# pin_matrix_schematic.net
KiCad netlist of a schematic drawn in EAGLE
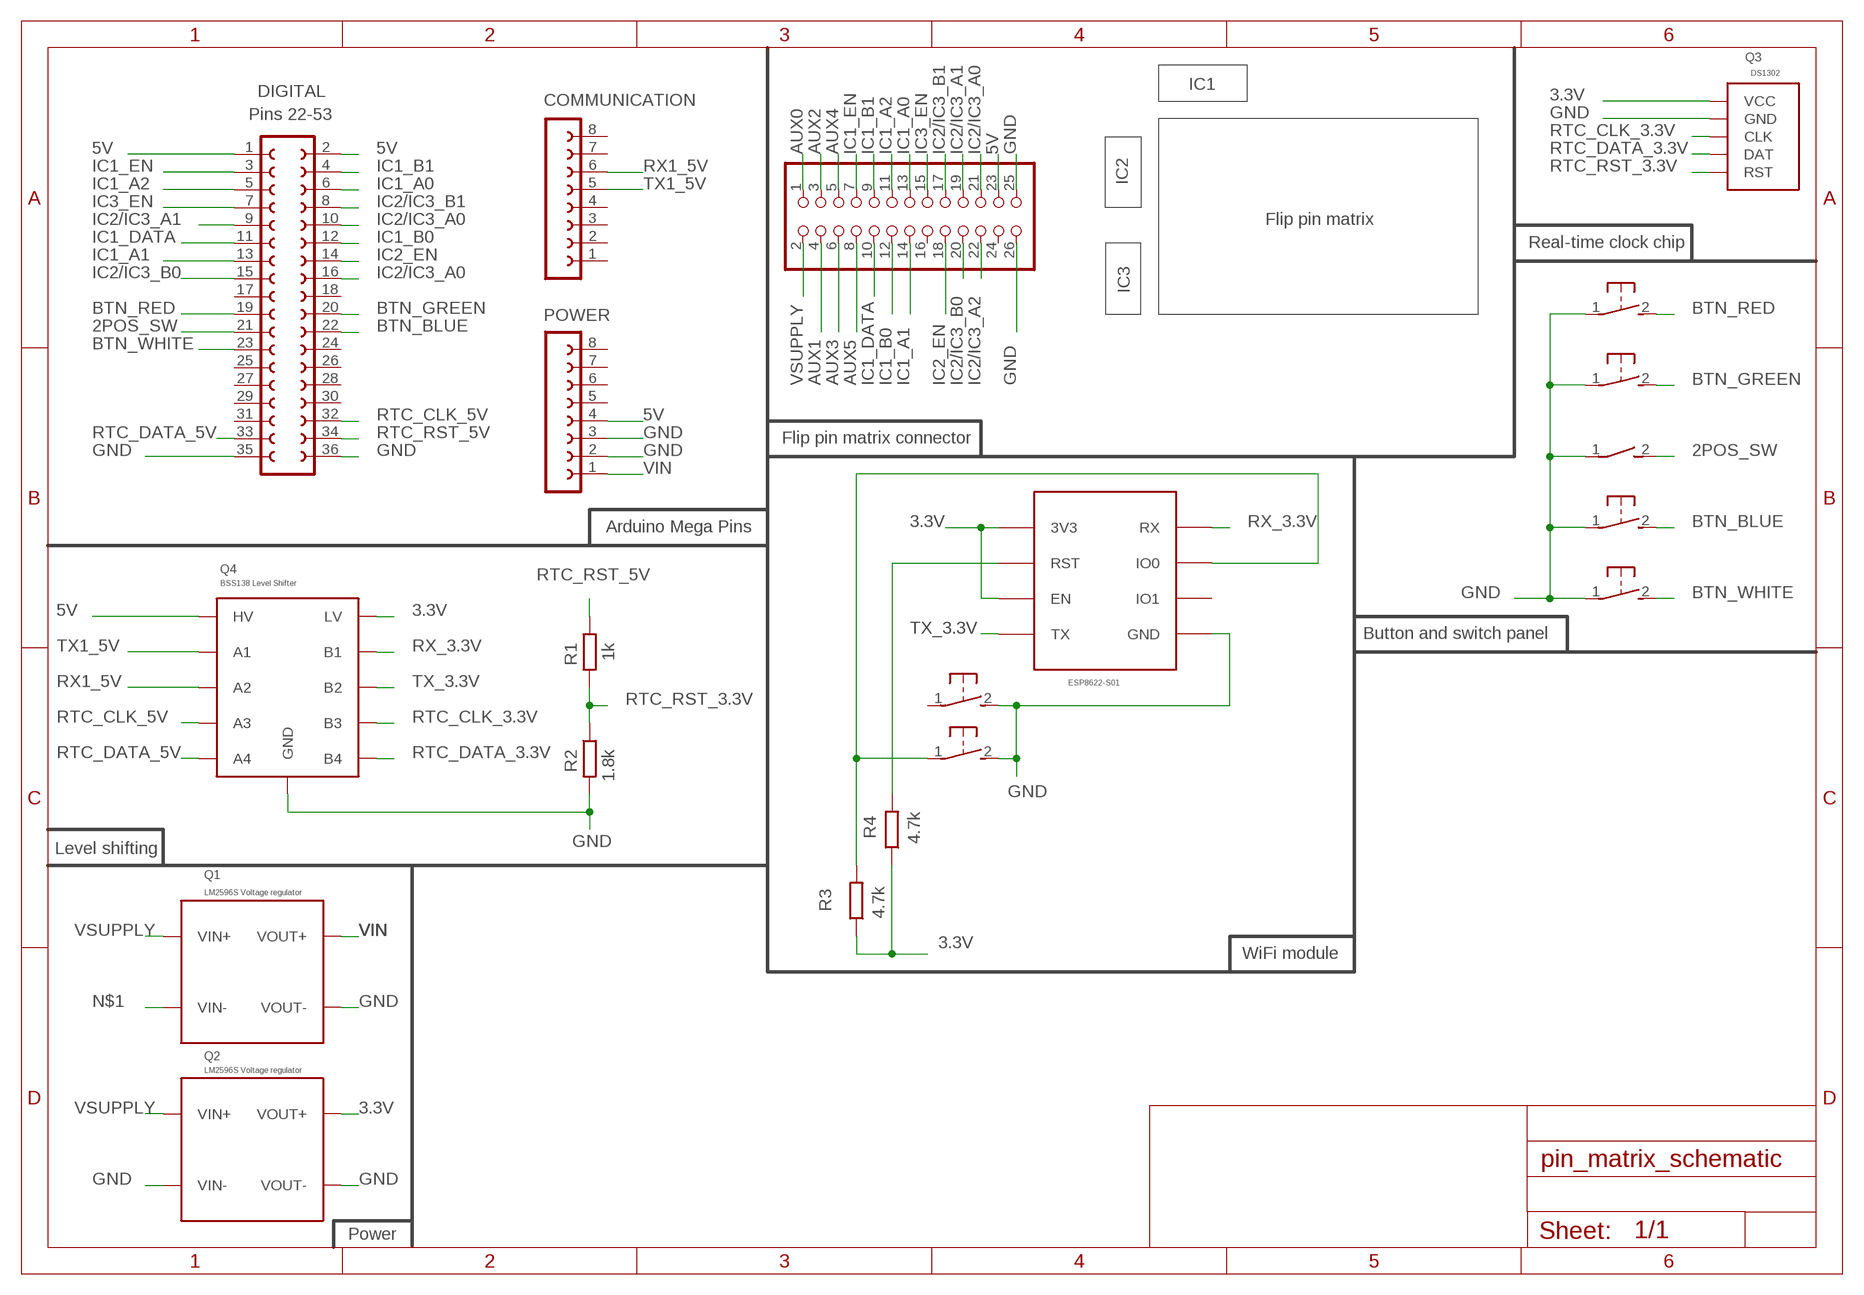
[diagram p0: schematic, sheet 1]

(export (version "E")
  (design (tool "Eeschema 10.0.6"))
  (components
    (comp (ref "COMMUNICATION")
      (value "FE08-1")
      (footprint "eagle-import:FE08")
      (libsource (lib "eagle-import") (part "FE08-1"))
    )
    (comp (ref "DIGITAL")
      (value "Pins 22-53")
      (footprint "eagle-import:FE18-2")
      (libsource (lib "eagle-import") (part "FE18-2"))
    )
    (comp (ref "JP1")
      (value "PINHD-2X13")
      (footprint "eagle-import:2X13")
      (libsource (lib "eagle-import") (part "PINHD-2X13"))
    )
    (comp (ref "POWER")
      (value "FE08-1")
      (footprint "eagle-import:FE08")
      (libsource (lib "eagle-import") (part "FE08-1"))
    )
    (comp (ref "Q1")
      (value "LM2596S-DCDC-BRD")
      (footprint "eagle-import:LM2596S-FOOT")
      (libsource (lib "eagle-import") (part "LM2596S-DCDC-BRD"))
    )
    (comp (ref "Q2")
      (value "LM2596S-DCDC-BRD")
      (footprint "eagle-import:LM2596S-FOOT")
      (libsource (lib "eagle-import") (part "LM2596S-DCDC-BRD"))
    )
    (comp (ref "Q3")
      (value "DS1302-BRD")
      (footprint "eagle-import:DS1302-FOOT")
      (libsource (lib "eagle-import") (part "DS1302-BRD"))
    )
    (comp (ref "Q4")
      (value "BSS138-4CH-LVL-BRD")
      (footprint "eagle-import:BSS138-LVL-FOOT")
      (libsource (lib "eagle-import") (part "BSS138-4CH-LVL-BRD"))
    )
    (comp (ref "Q5")
      (value "ESP1866-01S")
      (footprint "eagle-import:ESP8622-01S-FOOT")
      (libsource (lib "eagle-import") (part "ESP1866-01S"))
    )
    (comp (ref "R1")
      (value "1k")
      (footprint "eagle-import:0204_7")
      (libsource (lib "eagle-import") (part "R-EU_0204/7"))
    )
    (comp (ref "R2")
      (value "1.8k")
      (footprint "eagle-import:0204_7")
      (libsource (lib "eagle-import") (part "R-EU_0204/7"))
    )
    (comp (ref "R3")
      (value "4.7k")
      (footprint "eagle-import:0204_7")
      (libsource (lib "eagle-import") (part "R-EU_0204/7"))
    )
    (comp (ref "R4")
      (value "4.7k")
      (footprint "eagle-import:0204_7")
      (libsource (lib "eagle-import") (part "R-EU_0204/7"))
    )
    (comp (ref "S1")
      (value "DS01E")
      (footprint "eagle-import:DS-01")
      (libsource (lib "eagle-import") (part "DS01E"))
    )
    (comp (ref "S2")
      (value "31-XX")
      (footprint "eagle-import:B3F-31XX")
      (fields (field (name "MPN") "B3F-3100"))
      (libsource (lib "eagle-import") (part "31-XX"))
    )
    (comp (ref "S3")
      (value "31-XX")
      (footprint "eagle-import:B3F-31XX")
      (fields (field (name "MPN") "B3F-3100"))
      (libsource (lib "eagle-import") (part "31-XX"))
    )
    (comp (ref "S4")
      (value "31-XX")
      (footprint "eagle-import:B3F-31XX")
      (fields (field (name "MPN") "B3F-3100"))
      (libsource (lib "eagle-import") (part "31-XX"))
    )
    (comp (ref "S5")
      (value "31-XX")
      (footprint "eagle-import:B3F-31XX")
      (fields (field (name "MPN") "B3F-3100"))
      (libsource (lib "eagle-import") (part "31-XX"))
    )
    (comp (ref "S6")
      (value "31-XX")
      (footprint "eagle-import:B3F-31XX")
      (fields (field (name "MPN") "B3F-3100"))
      (libsource (lib "eagle-import") (part "31-XX"))
    )
    (comp (ref "S7")
      (value "31-XX")
      (footprint "eagle-import:B3F-31XX")
      (fields (field (name "MPN") "B3F-3100"))
      (libsource (lib "eagle-import") (part "31-XX"))
    )
  )
  (nets
    (net (code "1") (name "/2POS_SW") (class "Default")
      (node (ref "DIGITAL") (pin "21") (pinfunction "21_21") (pintype "passive"))
      (node (ref "S1") (pin "2") (pinfunction "2_2") (pintype "passive"))
    )
    (net (code "2") (name "/3.3V") (class "Default")
      (node (ref "Q2") (pin "VOUT+") (pinfunction "VOUT+_VOUT+") (pintype "power_in"))
      (node (ref "Q3") (pin "VCC") (pinfunction "VCC_VCC") (pintype "power_in"))
      (node (ref "Q4") (pin "LV") (pinfunction "LV_LV") (pintype "power_in"))
      (node (ref "Q5") (pin "3V3") (pinfunction "3V3_3V3") (pintype "power_in"))
      (node (ref "Q5") (pin "EN") (pinfunction "EN_EN") (pintype "input"))
      (node (ref "R3") (pin "1") (pinfunction "1_1") (pintype "passive"))
      (node (ref "R4") (pin "1") (pinfunction "1_1") (pintype "passive"))
    )
    (net (code "3") (name "/5V") (class "Default")
      (node (ref "DIGITAL") (pin "1") (pinfunction "1_1") (pintype "passive"))
      (node (ref "DIGITAL") (pin "2") (pinfunction "2_2") (pintype "passive"))
      (node (ref "JP1") (pin "23") (pinfunction "23_23") (pintype "passive"))
      (node (ref "POWER") (pin "4") (pinfunction "4_4") (pintype "passive"))
      (node (ref "Q4") (pin "HV") (pinfunction "HV_HV") (pintype "power_in"))
    )
    (net (code "4") (name "/AUX0") (class "Default")
      (node (ref "JP1") (pin "1") (pinfunction "1_1") (pintype "passive"))
    )
    (net (code "5") (name "/AUX1") (class "Default")
      (node (ref "JP1") (pin "4") (pinfunction "4_4") (pintype "passive"))
    )
    (net (code "6") (name "/AUX2") (class "Default")
      (node (ref "JP1") (pin "3") (pinfunction "3_3") (pintype "passive"))
    )
    (net (code "7") (name "/AUX3") (class "Default")
      (node (ref "JP1") (pin "6") (pinfunction "6_6") (pintype "passive"))
    )
    (net (code "8") (name "/AUX4") (class "Default")
      (node (ref "JP1") (pin "5") (pinfunction "5_5") (pintype "passive"))
    )
    (net (code "9") (name "/AUX5") (class "Default")
      (node (ref "JP1") (pin "8") (pinfunction "8_8") (pintype "passive"))
    )
    (net (code "10") (name "/BTN_BLUE") (class "Default")
      (node (ref "DIGITAL") (pin "22") (pinfunction "22_22") (pintype "passive"))
      (node (ref "S4") (pin "2") (pinfunction "S_2") (pintype "passive"))
    )
    (net (code "11") (name "/BTN_GREEN") (class "Default")
      (node (ref "DIGITAL") (pin "20") (pinfunction "20_20") (pintype "passive"))
      (node (ref "S3") (pin "2") (pinfunction "S_2") (pintype "passive"))
    )
    (net (code "12") (name "/BTN_RED") (class "Default")
      (node (ref "DIGITAL") (pin "19") (pinfunction "19_19") (pintype "passive"))
      (node (ref "S2") (pin "2") (pinfunction "S_2") (pintype "passive"))
    )
    (net (code "13") (name "/BTN_WHITE") (class "Default")
      (node (ref "DIGITAL") (pin "23") (pinfunction "23_23") (pintype "passive"))
      (node (ref "S5") (pin "2") (pinfunction "S_2") (pintype "passive"))
    )
    (net (code "14") (name "/GND") (class "Default")
      (node (ref "DIGITAL") (pin "35") (pinfunction "35_35") (pintype "passive"))
      (node (ref "DIGITAL") (pin "36") (pinfunction "36_36") (pintype "passive"))
      (node (ref "JP1") (pin "25") (pinfunction "25_25") (pintype "passive"))
      (node (ref "JP1") (pin "26") (pinfunction "26_26") (pintype "passive"))
      (node (ref "POWER") (pin "2") (pinfunction "2_2") (pintype "passive"))
      (node (ref "POWER") (pin "3") (pinfunction "3_3") (pintype "passive"))
      (node (ref "Q1") (pin "VOUT-") (pinfunction "VOUT-_VOUT-") (pintype "power_in"))
      (node (ref "Q2") (pin "VIN-") (pinfunction "VIN-_VIN-") (pintype "power_in"))
      (node (ref "Q2") (pin "VOUT-") (pinfunction "VOUT-_VOUT-") (pintype "power_in"))
      (node (ref "Q3") (pin "GND") (pinfunction "GND_GND") (pintype "power_in"))
      (node (ref "Q4") (pin "GND_HV") (pinfunction "GND_GND_HV") (pintype "power_in"))
      (node (ref "Q4") (pin "GND_LV") (pinfunction "GND_GND_LV") (pintype "power_in"))
      (node (ref "Q5") (pin "GND") (pinfunction "GND_GND") (pintype "power_in"))
      (node (ref "R2") (pin "2") (pinfunction "2_2") (pintype "passive"))
      (node (ref "S1") (pin "1") (pinfunction "1_1") (pintype "passive"))
      (node (ref "S2") (pin "1") (pinfunction "P_1") (pintype "passive"))
      (node (ref "S3") (pin "1") (pinfunction "P_1") (pintype "passive"))
      (node (ref "S4") (pin "1") (pinfunction "P_1") (pintype "passive"))
      (node (ref "S5") (pin "1") (pinfunction "P_1") (pintype "passive"))
      (node (ref "S6") (pin "2") (pinfunction "S_2") (pintype "passive"))
      (node (ref "S7") (pin "2") (pinfunction "S_2") (pintype "passive"))
    )
    (net (code "15") (name "/IC1_A0") (class "Default")
      (node (ref "DIGITAL") (pin "6") (pinfunction "6_6") (pintype "passive"))
      (node (ref "JP1") (pin "13") (pinfunction "13_13") (pintype "passive"))
    )
    (net (code "16") (name "/IC1_A1") (class "Default")
      (node (ref "DIGITAL") (pin "13") (pinfunction "13_13") (pintype "passive"))
      (node (ref "JP1") (pin "14") (pinfunction "14_14") (pintype "passive"))
    )
    (net (code "17") (name "/IC1_A2") (class "Default")
      (node (ref "DIGITAL") (pin "5") (pinfunction "5_5") (pintype "passive"))
      (node (ref "JP1") (pin "11") (pinfunction "11_11") (pintype "passive"))
    )
    (net (code "18") (name "/IC1_B0") (class "Default")
      (node (ref "DIGITAL") (pin "12") (pinfunction "12_12") (pintype "passive"))
      (node (ref "JP1") (pin "12") (pinfunction "12_12") (pintype "passive"))
    )
    (net (code "19") (name "/IC1_B1") (class "Default")
      (node (ref "DIGITAL") (pin "4") (pinfunction "4_4") (pintype "passive"))
      (node (ref "JP1") (pin "9") (pinfunction "9_9") (pintype "passive"))
    )
    (net (code "20") (name "/IC1_DATA") (class "Default")
      (node (ref "DIGITAL") (pin "11") (pinfunction "11_11") (pintype "passive"))
      (node (ref "JP1") (pin "10") (pinfunction "10_10") (pintype "passive"))
    )
    (net (code "21") (name "/IC1_EN") (class "Default")
      (node (ref "DIGITAL") (pin "3") (pinfunction "3_3") (pintype "passive"))
      (node (ref "JP1") (pin "7") (pinfunction "7_7") (pintype "passive"))
    )
    (net (code "22") (name "/IC2_EN") (class "Default")
      (node (ref "DIGITAL") (pin "14") (pinfunction "14_14") (pintype "passive"))
      (node (ref "JP1") (pin "18") (pinfunction "18_18") (pintype "passive"))
    )
    (net (code "23") (name "/IC2{slash}IC3_A0") (class "Default")
      (node (ref "DIGITAL") (pin "10") (pinfunction "10_10") (pintype "passive"))
      (node (ref "DIGITAL") (pin "16") (pinfunction "16_16") (pintype "passive"))
      (node (ref "JP1") (pin "21") (pinfunction "21_21") (pintype "passive"))
    )
    (net (code "24") (name "/IC2{slash}IC3_A1") (class "Default")
      (node (ref "DIGITAL") (pin "9") (pinfunction "9_9") (pintype "passive"))
      (node (ref "JP1") (pin "19") (pinfunction "19_19") (pintype "passive"))
    )
    (net (code "25") (name "/IC2{slash}IC3_A2") (class "Default")
      (node (ref "JP1") (pin "22") (pinfunction "22_22") (pintype "passive"))
    )
    (net (code "26") (name "/IC2{slash}IC3_B0") (class "Default")
      (node (ref "DIGITAL") (pin "15") (pinfunction "15_15") (pintype "passive"))
      (node (ref "JP1") (pin "20") (pinfunction "20_20") (pintype "passive"))
    )
    (net (code "27") (name "/IC2{slash}IC3_B1") (class "Default")
      (node (ref "DIGITAL") (pin "8") (pinfunction "8_8") (pintype "passive"))
      (node (ref "JP1") (pin "17") (pinfunction "17_17") (pintype "passive"))
    )
    (net (code "28") (name "/IC3_EN") (class "Default")
      (node (ref "DIGITAL") (pin "7") (pinfunction "7_7") (pintype "passive"))
      (node (ref "JP1") (pin "15") (pinfunction "15_15") (pintype "passive"))
    )
    (net (code "29") (name "/N$1") (class "Default")
      (node (ref "Q1") (pin "VIN-") (pinfunction "VIN-_VIN-") (pintype "power_in"))
    )
    (net (code "30") (name "/RTC_CLK_3.3V") (class "Default")
      (node (ref "Q3") (pin "CLK") (pinfunction "CLK_CLK") (pintype "input"))
      (node (ref "Q4") (pin "B3") (pinfunction "B3_B3") (pintype "bidirectional"))
    )
    (net (code "31") (name "/RTC_CLK_5V") (class "Default")
      (node (ref "DIGITAL") (pin "32") (pinfunction "32_32") (pintype "passive"))
      (node (ref "Q4") (pin "A3") (pinfunction "A3_A3") (pintype "bidirectional"))
    )
    (net (code "32") (name "/RTC_DATA_3.3V") (class "Default")
      (node (ref "Q3") (pin "DAT") (pinfunction "DAT_DAT") (pintype "bidirectional"))
      (node (ref "Q4") (pin "B4") (pinfunction "B4_B4") (pintype "bidirectional"))
    )
    (net (code "33") (name "/RTC_DATA_5V") (class "Default")
      (node (ref "DIGITAL") (pin "33") (pinfunction "33_33") (pintype "passive"))
      (node (ref "Q4") (pin "A4") (pinfunction "A4_A4") (pintype "bidirectional"))
    )
    (net (code "34") (name "/RTC_RST_3.3V") (class "Default")
      (node (ref "Q3") (pin "RST") (pinfunction "RST_RST") (pintype "input"))
      (node (ref "R1") (pin "2") (pinfunction "2_2") (pintype "passive"))
      (node (ref "R2") (pin "1") (pinfunction "1_1") (pintype "passive"))
    )
    (net (code "35") (name "/RTC_RST_5V") (class "Default")
      (node (ref "DIGITAL") (pin "34") (pinfunction "34_34") (pintype "passive"))
      (node (ref "R1") (pin "1") (pinfunction "1_1") (pintype "passive"))
    )
    (net (code "36") (name "/RX1_5V") (class "Default")
      (node (ref "COMMUNICATION") (pin "6") (pinfunction "6_6") (pintype "passive"))
      (node (ref "Q4") (pin "A2") (pinfunction "A2_A2") (pintype "bidirectional"))
    )
    (net (code "37") (name "/RX_3.3V") (class "Default")
      (node (ref "Q4") (pin "B1") (pinfunction "B1_B1") (pintype "bidirectional"))
      (node (ref "Q5") (pin "RX") (pinfunction "RX_RX") (pintype "input"))
    )
    (net (code "38") (name "/TX1_5V") (class "Default")
      (node (ref "COMMUNICATION") (pin "5") (pinfunction "5_5") (pintype "passive"))
      (node (ref "Q4") (pin "A1") (pinfunction "A1_A1") (pintype "bidirectional"))
    )
    (net (code "39") (name "/TX_3.3V") (class "Default")
      (node (ref "Q4") (pin "B2") (pinfunction "B2_B2") (pintype "bidirectional"))
      (node (ref "Q5") (pin "TX") (pinfunction "TX_TX") (pintype "output"))
    )
    (net (code "40") (name "/VIN") (class "Default")
      (node (ref "POWER") (pin "1") (pinfunction "1_1") (pintype "passive"))
      (node (ref "Q1") (pin "VOUT+") (pinfunction "VOUT+_VOUT+") (pintype "power_in"))
    )
    (net (code "41") (name "/VSUPPLY") (class "Default")
      (node (ref "JP1") (pin "2") (pinfunction "2_2") (pintype "passive"))
      (node (ref "Q1") (pin "VIN+") (pinfunction "VIN+_VIN+") (pintype "power_in"))
      (node (ref "Q2") (pin "VIN+") (pinfunction "VIN+_VIN+") (pintype "power_in"))
    )
    (net (code "42") (name "Net-(Q5-PadRST)") (class "Default")
      (node (ref "Q5") (pin "RST") (pinfunction "RST_RST") (pintype "input"))
      (node (ref "R4") (pin "2") (pinfunction "2_2") (pintype "passive"))
    )
    (net (code "43") (name "Net-(S6-P)") (class "Default")
      (node (ref "Q5") (pin "IO0") (pinfunction "IO0_IO0") (pintype "bidirectional"))
      (node (ref "R3") (pin "2") (pinfunction "2_2") (pintype "passive"))
      (node (ref "S6") (pin "1") (pinfunction "P_1") (pintype "passive"))
    )
    (net (code "44") (name "unconnected-(COMMUNICATION-Pad1)") (class "Default")
      (node (ref "COMMUNICATION") (pin "1") (pinfunction "1_1") (pintype "passive"))
    )
    (net (code "45") (name "unconnected-(COMMUNICATION-Pad2)") (class "Default")
      (node (ref "COMMUNICATION") (pin "2") (pinfunction "2_2") (pintype "passive"))
    )
    (net (code "46") (name "unconnected-(COMMUNICATION-Pad3)") (class "Default")
      (node (ref "COMMUNICATION") (pin "3") (pinfunction "3_3") (pintype "passive"))
    )
    (net (code "47") (name "unconnected-(COMMUNICATION-Pad4)") (class "Default")
      (node (ref "COMMUNICATION") (pin "4") (pinfunction "4_4") (pintype "passive"))
    )
    (net (code "48") (name "unconnected-(COMMUNICATION-Pad7)") (class "Default")
      (node (ref "COMMUNICATION") (pin "7") (pinfunction "7_7") (pintype "passive"))
    )
    (net (code "49") (name "unconnected-(COMMUNICATION-Pad8)") (class "Default")
      (node (ref "COMMUNICATION") (pin "8") (pinfunction "8_8") (pintype "passive"))
    )
    (net (code "50") (name "unconnected-(DIGITAL-Pad17)") (class "Default")
      (node (ref "DIGITAL") (pin "17") (pinfunction "17_17") (pintype "passive"))
    )
    (net (code "51") (name "unconnected-(DIGITAL-Pad18)") (class "Default")
      (node (ref "DIGITAL") (pin "18") (pinfunction "18_18") (pintype "passive"))
    )
    (net (code "52") (name "unconnected-(DIGITAL-Pad24)") (class "Default")
      (node (ref "DIGITAL") (pin "24") (pinfunction "24_24") (pintype "passive"))
    )
    (net (code "53") (name "unconnected-(DIGITAL-Pad25)") (class "Default")
      (node (ref "DIGITAL") (pin "25") (pinfunction "25_25") (pintype "passive"))
    )
    (net (code "54") (name "unconnected-(DIGITAL-Pad26)") (class "Default")
      (node (ref "DIGITAL") (pin "26") (pinfunction "26_26") (pintype "passive"))
    )
    (net (code "55") (name "unconnected-(DIGITAL-Pad27)") (class "Default")
      (node (ref "DIGITAL") (pin "27") (pinfunction "27_27") (pintype "passive"))
    )
    (net (code "56") (name "unconnected-(DIGITAL-Pad28)") (class "Default")
      (node (ref "DIGITAL") (pin "28") (pinfunction "28_28") (pintype "passive"))
    )
    (net (code "57") (name "unconnected-(DIGITAL-Pad29)") (class "Default")
      (node (ref "DIGITAL") (pin "29") (pinfunction "29_29") (pintype "passive"))
    )
    (net (code "58") (name "unconnected-(DIGITAL-Pad30)") (class "Default")
      (node (ref "DIGITAL") (pin "30") (pinfunction "30_30") (pintype "passive"))
    )
    (net (code "59") (name "unconnected-(DIGITAL-Pad31)") (class "Default")
      (node (ref "DIGITAL") (pin "31") (pinfunction "31_31") (pintype "passive"))
    )
    (net (code "60") (name "unconnected-(JP1-Pad16)") (class "Default")
      (node (ref "JP1") (pin "16") (pinfunction "16_16") (pintype "passive"))
    )
    (net (code "61") (name "unconnected-(JP1-Pad24)") (class "Default")
      (node (ref "JP1") (pin "24") (pinfunction "24_24") (pintype "passive"))
    )
    (net (code "62") (name "unconnected-(POWER-Pad5)") (class "Default")
      (node (ref "POWER") (pin "5") (pinfunction "5_5") (pintype "passive"))
    )
    (net (code "63") (name "unconnected-(POWER-Pad6)") (class "Default")
      (node (ref "POWER") (pin "6") (pinfunction "6_6") (pintype "passive"))
    )
    (net (code "64") (name "unconnected-(POWER-Pad7)") (class "Default")
      (node (ref "POWER") (pin "7") (pinfunction "7_7") (pintype "passive"))
    )
    (net (code "65") (name "unconnected-(POWER-Pad8)") (class "Default")
      (node (ref "POWER") (pin "8") (pinfunction "8_8") (pintype "passive"))
    )
    (net (code "66") (name "unconnected-(Q5-PadIO1)") (class "Default")
      (node (ref "Q5") (pin "IO1") (pinfunction "IO1_IO1") (pintype "bidirectional"))
    )
    (net (code "67") (name "unconnected-(S7-P-Pad1)") (class "Default")
      (node (ref "S7") (pin "1") (pinfunction "P_1") (pintype "passive"))
    )
  )
)
